# nRF5340.net
KiCad netlist of a schematic drawn in Altium Designer
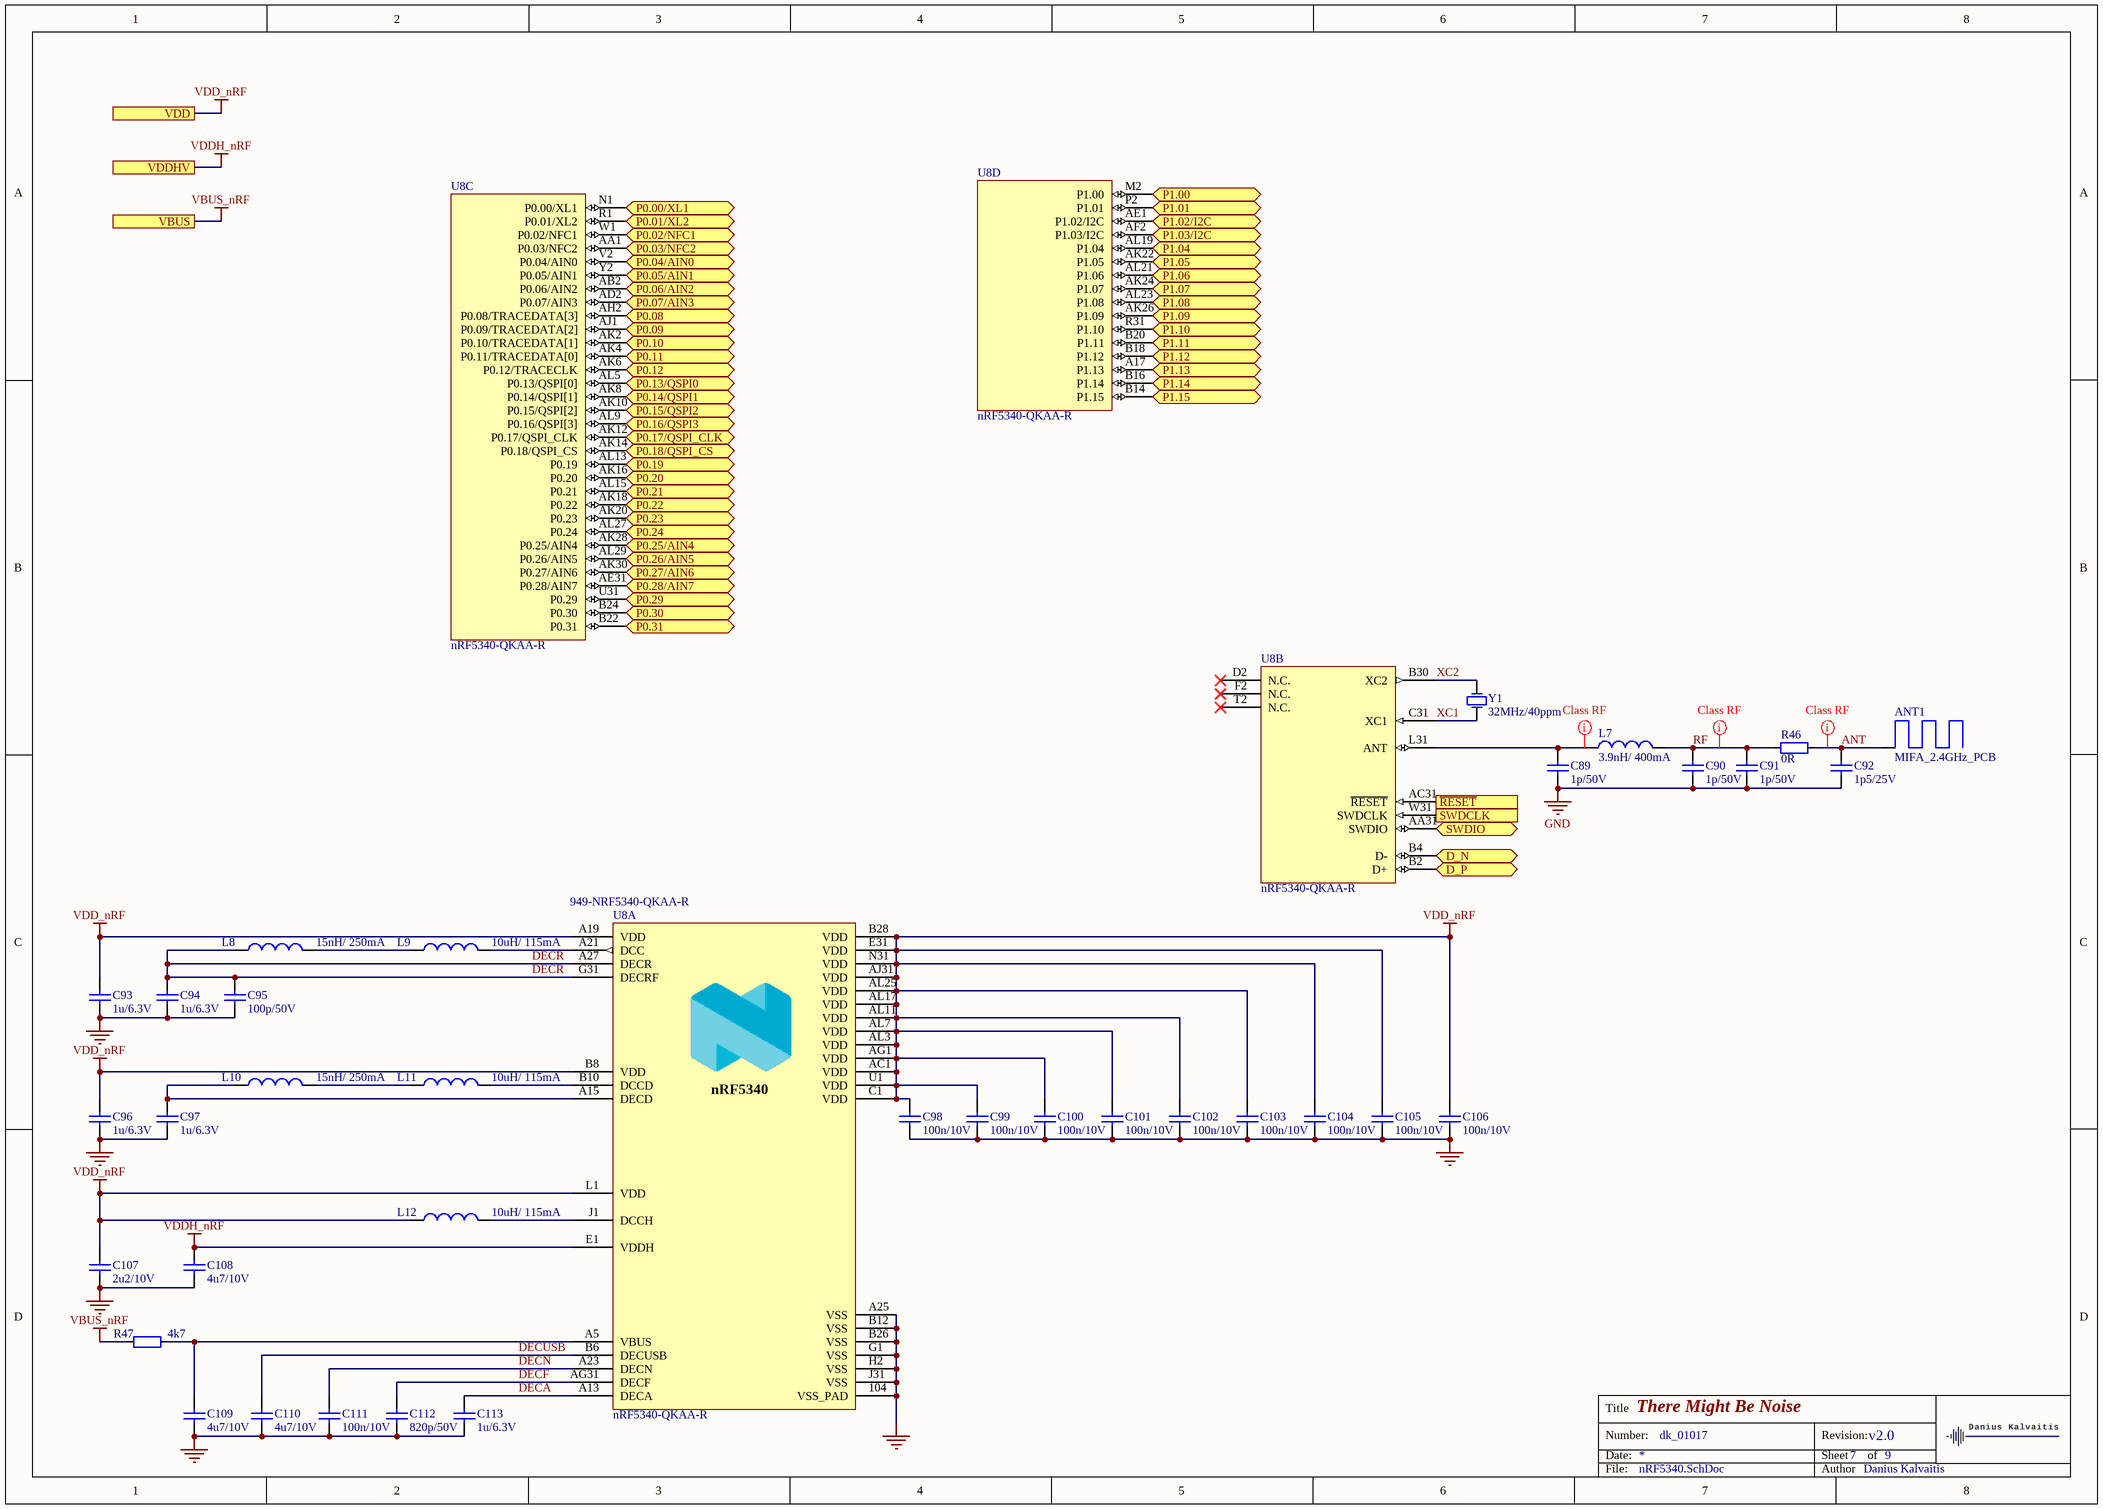
[diagram p0: nRF5340.SchDoc]

(export (version "E")
  (design (tool "Eeschema 10.0.6"))
  (components
    (comp (ref "ANT1")
      (value "MIFA_2.4GHz_PCB")
      (footprint "MIFA_2.4GHz_PCB2")
      (description "Meandered Inverted-F Antenna (MIFA)")
      (libsource (lib "altium-import") (part "root_0_MIFA_2.4GHz_PCB2_"))
    )
    (comp (ref "C89")
      (value "1p/50V")
      (footprint "C0201")
      (fields (field (name "VOLTAGE") "50V") (field (name "TOLERANCE") "10%"))
      (libsource (lib "dk_capacitors") (part "1p 50V C0G 0201"))
    )
    (comp (ref "C90")
      (value "1p/50V")
      (footprint "C0201")
      (fields (field (name "VOLTAGE") "50V") (field (name "TOLERANCE") "10%"))
      (libsource (lib "dk_capacitors") (part "1p 50V C0G 0201"))
    )
    (comp (ref "C91")
      (value "1p/50V")
      (footprint "C0201")
      (fields (field (name "VOLTAGE") "50V") (field (name "TOLERANCE") "10%"))
      (libsource (lib "dk_capacitors") (part "1p 50V C0G 0201"))
    )
    (comp (ref "C92")
      (value "1p5/25V")
      (footprint "C0201")
      (fields (field (name "VOLTAGE") "25V") (field (name "TOLERANCE") "7%"))
      (libsource (lib "dk_capacitors") (part "1p5 25V C0G 0201"))
    )
    (comp (ref "C93")
      (value "1u/6.3V")
      (footprint "C0402")
      (fields (field (name "VOLTAGE") "6.3V") (field (name "TOLERANCE") "10%"))
      (libsource (lib "dk_capacitors") (part "1u 6V3 X7R 0402"))
    )
    (comp (ref "C94")
      (value "1u/6.3V")
      (footprint "C0402")
      (fields (field (name "VOLTAGE") "6.3V") (field (name "TOLERANCE") "10%"))
      (libsource (lib "dk_capacitors") (part "1u 6V3 X7R 0402"))
    )
    (comp (ref "C95")
      (value "100p/50V")
      (footprint "C0201")
      (fields (field (name "VOLTAGE") "50V") (field (name "TOLERANCE") "10%"))
      (libsource (lib "dk_capacitors") (part "100p 50V X7R 0201"))
    )
    (comp (ref "C96")
      (value "1u/6.3V")
      (footprint "C0402")
      (fields (field (name "VOLTAGE") "6.3V") (field (name "TOLERANCE") "10%"))
      (libsource (lib "dk_capacitors") (part "1u 6V3 X7R 0402"))
    )
    (comp (ref "C97")
      (value "1u/6.3V")
      (footprint "C0402")
      (fields (field (name "VOLTAGE") "6.3V") (field (name "TOLERANCE") "10%"))
      (libsource (lib "dk_capacitors") (part "1u 6V3 X7R 0402"))
    )
    (comp (ref "C98")
      (value "100n/10V")
      (footprint "C0201")
      (fields (field (name "VOLTAGE") "10V") (field (name "TOLERANCE") "10%"))
      (libsource (lib "dk_capacitors") (part "100n 10V X5R 0201"))
    )
    (comp (ref "C99")
      (value "100n/10V")
      (footprint "C0201")
      (fields (field (name "VOLTAGE") "10V") (field (name "TOLERANCE") "10%"))
      (libsource (lib "dk_capacitors") (part "100n 10V X5R 0201"))
    )
    (comp (ref "C100")
      (value "100n/10V")
      (footprint "C0201")
      (fields (field (name "VOLTAGE") "10V") (field (name "TOLERANCE") "10%"))
      (libsource (lib "dk_capacitors") (part "100n 10V X5R 0201"))
    )
    (comp (ref "C101")
      (value "100n/10V")
      (footprint "C0201")
      (fields (field (name "VOLTAGE") "10V") (field (name "TOLERANCE") "10%"))
      (libsource (lib "dk_capacitors") (part "100n 10V X5R 0201"))
    )
    (comp (ref "C102")
      (value "100n/10V")
      (footprint "C0201")
      (fields (field (name "VOLTAGE") "10V") (field (name "TOLERANCE") "10%"))
      (libsource (lib "dk_capacitors") (part "100n 10V X5R 0201"))
    )
    (comp (ref "C103")
      (value "100n/10V")
      (footprint "C0201")
      (fields (field (name "VOLTAGE") "10V") (field (name "TOLERANCE") "10%"))
      (libsource (lib "dk_capacitors") (part "100n 10V X5R 0201"))
    )
    (comp (ref "C104")
      (value "100n/10V")
      (footprint "C0201")
      (fields (field (name "VOLTAGE") "10V") (field (name "TOLERANCE") "10%"))
      (libsource (lib "dk_capacitors") (part "100n 10V X5R 0201"))
    )
    (comp (ref "C105")
      (value "100n/10V")
      (footprint "C0201")
      (fields (field (name "VOLTAGE") "10V") (field (name "TOLERANCE") "10%"))
      (libsource (lib "dk_capacitors") (part "100n 10V X5R 0201"))
    )
    (comp (ref "C106")
      (value "100n/10V")
      (footprint "C0201")
      (fields (field (name "VOLTAGE") "10V") (field (name "TOLERANCE") "10%"))
      (libsource (lib "dk_capacitors") (part "100n 10V X5R 0201"))
    )
    (comp (ref "C107")
      (value "2u2/10V")
      (footprint "C0603")
      (fields (field (name "VOLTAGE") "10V") (field (name "TOLERANCE") "10%"))
      (libsource (lib "dk_capacitors") (part "2u2 10V X5R 0603"))
    )
    (comp (ref "C108")
      (value "4u7/10V")
      (footprint "C0603")
      (fields (field (name "VOLTAGE") "10V") (field (name "TOLERANCE") "10%"))
      (libsource (lib "dk_capacitors") (part "4u7 10V X5R 0603"))
    )
    (comp (ref "C109")
      (value "4u7/10V")
      (footprint "C0603")
      (fields (field (name "VOLTAGE") "10V") (field (name "TOLERANCE") "10%"))
      (libsource (lib "dk_capacitors") (part "4u7 10V X5R 0603"))
    )
    (comp (ref "C110")
      (value "4u7/10V")
      (footprint "C0603")
      (fields (field (name "VOLTAGE") "10V") (field (name "TOLERANCE") "10%"))
      (libsource (lib "dk_capacitors") (part "4u7 10V X5R 0603"))
    )
    (comp (ref "C111")
      (value "100n/10V")
      (footprint "C0201")
      (fields (field (name "VOLTAGE") "10V") (field (name "TOLERANCE") "10%"))
      (libsource (lib "dk_capacitors") (part "100n 10V X5R 0201"))
    )
    (comp (ref "C112")
      (value "820p/50V")
      (footprint "C0201")
      (fields (field (name "VOLTAGE") "50V") (field (name "TOLERANCE") "10%"))
      (libsource (lib "dk_capacitors") (part "820p 50V X7R 0201"))
    )
    (comp (ref "C113")
      (value "1u/6.3V")
      (footprint "C0402")
      (fields (field (name "VOLTAGE") "6.3V") (field (name "TOLERANCE") "10%"))
      (libsource (lib "dk_capacitors") (part "1u 6V3 X7R 0402"))
    )
    (comp (ref "L7")
      (value "3.9nH/ 400mA")
      (footprint "L0201")
      (description "Fixed Inductors IND 0201 3.9nH Hi-Q SMD RF IND")
      (fields (field (name "TOLERANCE") "10%"))
      (libsource (lib "dk_inductors") (part "MLG0603P3N9ST000"))
    )
    (comp (ref "L8")
      (value "15nH/ 250mA")
      (footprint "L0201")
      (description "Fixed Inductors IND 0201 15nH Hi-Q SMD RF IND")
      (fields (field (name "TOLERANCE") "3%"))
      (libsource (lib "dk_inductors") (part "MLG0603P15NHT000"))
    )
    (comp (ref "L9")
      (value "10uH/ 115mA")
      (footprint "L0603")
      (description "Fixed Inductors 10uH 10% Wound Chip")
      (fields (field (name "TOLERANCE") "10%"))
      (libsource (lib "altium-import") (part "root_0_L0603B100KDWFT_"))
    )
    (comp (ref "L10")
      (value "15nH/ 250mA")
      (footprint "L0201")
      (description "Fixed Inductors IND 0201 15nH Hi-Q SMD RF IND")
      (fields (field (name "TOLERANCE") "3%"))
      (libsource (lib "dk_inductors") (part "MLG0603P15NHT000"))
    )
    (comp (ref "L11")
      (value "10uH/ 115mA")
      (footprint "L0603")
      (description "Fixed Inductors 10uH 10% Wound Chip")
      (fields (field (name "TOLERANCE") "10%"))
      (libsource (lib "altium-import") (part "root_0_L0603B100KDWFT_"))
    )
    (comp (ref "L12")
      (value "10uH/ 115mA")
      (footprint "L0603")
      (description "Fixed Inductors 10uH 10% Wound Chip")
      (fields (field (name "TOLERANCE") "10%"))
      (libsource (lib "altium-import") (part "root_0_L0603B100KDWFT_"))
    )
    (comp (ref "R46")
      (value "0R")
      (footprint "R0201")
      (fields (field (name "TOLERANCE") "1%") (field (name "VOLTAGE") "25V"))
      (libsource (lib "dk_resistors") (part "0R 50mW 25V 0201"))
    )
    (comp (ref "R47")
      (value "4k7")
      (footprint "R0402")
      (fields (field (name "TOLERANCE") "1%") (field (name "VOLTAGE") "50V"))
      (libsource (lib "dk_resistors") (part "4k7 63mW 50V 0402"))
    )
    (comp (ref "U8")
      (value "nRF5340-QKAA-R")
      (footprint "AQFN-94")
      (description "Multi-protocol Bluetooth Low Energy, IEEE 802.15.4, ANT and 2.4GHz proprietary system-on-chip")
      (fields (field (name "SUPPLIER PART NUMBER 1") "949-NRF5340-QKAA-R"))
      (libsource (lib "dk_ic_microcontrollers") (part "nRF5340-QKAA-R"))
    )
    (comp (ref "Y1")
      (value "32MHz/40ppm")
      (footprint "XTAL_2X1_6")
      (description "Crystals 2x1.6mm 32MHz 40ppm Crystal Unit")
      (fields (field (name "TOLERANCE") "40ppm"))
      (libsource (lib "dk_timing") (part "XRCGB32M000FXH2CR0"))
    )
  )
  (nets
    (net (code "1") (name "/ANT") (class "Default")
      (node (ref "ANT1") (pin "1") (pinfunction "1_1") (pintype "passive"))
      (node (ref "C92") (pin "2") (pinfunction "2_2") (pintype "passive"))
      (node (ref "R46") (pin "2") (pinfunction "2_2") (pintype "passive"))
    )
    (net (code "2") (name "/DECA") (class "Default")
      (node (ref "C113") (pin "2") (pinfunction "2_2") (pintype "passive"))
      (node (ref "U8") (pin "A13") (pinfunction "DECA_A13") (pintype "power_in"))
    )
    (net (code "3") (name "/DECF") (class "Default")
      (node (ref "C112") (pin "2") (pinfunction "2_2") (pintype "passive"))
      (node (ref "U8") (pin "AG31") (pinfunction "DECF_AG31") (pintype "power_in"))
    )
    (net (code "4") (name "/DECN") (class "Default")
      (node (ref "C111") (pin "2") (pinfunction "2_2") (pintype "passive"))
      (node (ref "U8") (pin "A23") (pinfunction "DECN_A23") (pintype "power_in"))
    )
    (net (code "5") (name "/DECR") (class "Default")
      (node (ref "C94") (pin "2") (pinfunction "2_2") (pintype "passive"))
      (node (ref "C95") (pin "2") (pinfunction "2_2") (pintype "passive"))
      (node (ref "L8") (pin "1") (pinfunction "1_1") (pintype "passive"))
      (node (ref "U8") (pin "A27") (pinfunction "DECR_A27") (pintype "power_in"))
      (node (ref "U8") (pin "G31") (pinfunction "DECRF_G31") (pintype "power_in"))
    )
    (net (code "6") (name "/DECUSB") (class "Default")
      (node (ref "C110") (pin "2") (pinfunction "2_2") (pintype "passive"))
      (node (ref "U8") (pin "B6") (pinfunction "DECUSB_B6") (pintype "power_in"))
    )
    (net (code "7") (name "/D_N") (class "Default")
      (node (ref "U8") (pin "B4") (pinfunction "D-_B4") (pintype "bidirectional"))
    )
    (net (code "8") (name "/D_P") (class "Default")
      (node (ref "U8") (pin "B2") (pinfunction "D+_B2") (pintype "bidirectional"))
    )
    (net (code "9") (name "/P0.00{slash}XL1") (class "Default")
      (node (ref "U8") (pin "N1") (pinfunction "P0.00/XL1_N1") (pintype "bidirectional"))
    )
    (net (code "10") (name "/P0.01{slash}XL2") (class "Default")
      (node (ref "U8") (pin "R1") (pinfunction "P0.01/XL2_R1") (pintype "bidirectional"))
    )
    (net (code "11") (name "/P0.02{slash}NFC1") (class "Default")
      (node (ref "U8") (pin "W1") (pinfunction "P0.02/NFC1_W1") (pintype "bidirectional"))
    )
    (net (code "12") (name "/P0.03{slash}NFC2") (class "Default")
      (node (ref "U8") (pin "AA1") (pinfunction "P0.03/NFC2_AA1") (pintype "bidirectional"))
    )
    (net (code "13") (name "/P0.04{slash}AIN0") (class "Default")
      (node (ref "U8") (pin "V2") (pinfunction "P0.04/AIN0_V2") (pintype "bidirectional"))
    )
    (net (code "14") (name "/P0.05{slash}AIN1") (class "Default")
      (node (ref "U8") (pin "Y2") (pinfunction "P0.05/AIN1_Y2") (pintype "bidirectional"))
    )
    (net (code "15") (name "/P0.06{slash}AIN2") (class "Default")
      (node (ref "U8") (pin "AB2") (pinfunction "P0.06/AIN2_AB2") (pintype "bidirectional"))
    )
    (net (code "16") (name "/P0.07{slash}AIN3") (class "Default")
      (node (ref "U8") (pin "AD2") (pinfunction "P0.07/AIN3_AD2") (pintype "bidirectional"))
    )
    (net (code "17") (name "/P0.08") (class "Default")
      (node (ref "U8") (pin "AH2") (pinfunction "P0.08/TRACEDATA[3]_AH2") (pintype "bidirectional"))
    )
    (net (code "18") (name "/P0.09") (class "Default")
      (node (ref "U8") (pin "AJ1") (pinfunction "P0.09/TRACEDATA[2]_AJ1") (pintype "bidirectional"))
    )
    (net (code "19") (name "/P0.10") (class "Default")
      (node (ref "U8") (pin "AK2") (pinfunction "P0.10/TRACEDATA[1]_AK2") (pintype "bidirectional"))
    )
    (net (code "20") (name "/P0.11") (class "Default")
      (node (ref "U8") (pin "AK4") (pinfunction "P0.11/TRACEDATA[0]_AK4") (pintype "bidirectional"))
    )
    (net (code "21") (name "/P0.12") (class "Default")
      (node (ref "U8") (pin "AK6") (pinfunction "P0.12/TRACECLK_AK6") (pintype "bidirectional"))
    )
    (net (code "22") (name "/P0.13{slash}QSPI0") (class "Default")
      (node (ref "U8") (pin "AL5") (pinfunction "P0.13/QSPI[0]_AL5") (pintype "bidirectional"))
    )
    (net (code "23") (name "/P0.14{slash}QSPI1") (class "Default")
      (node (ref "U8") (pin "AK8") (pinfunction "P0.14/QSPI[1]_AK8") (pintype "bidirectional"))
    )
    (net (code "24") (name "/P0.15{slash}QSPI2") (class "Default")
      (node (ref "U8") (pin "AK10") (pinfunction "P0.15/QSPI[2]_AK10") (pintype "bidirectional"))
    )
    (net (code "25") (name "/P0.16{slash}QSPI3") (class "Default")
      (node (ref "U8") (pin "AL9") (pinfunction "P0.16/QSPI[3]_AL9") (pintype "bidirectional"))
    )
    (net (code "26") (name "/P0.17{slash}QSPI_CLK") (class "Default")
      (node (ref "U8") (pin "AK12") (pinfunction "P0.17/QSPI_CLK_AK12") (pintype "bidirectional"))
    )
    (net (code "27") (name "/P0.18{slash}QSPI_CS") (class "Default")
      (node (ref "U8") (pin "AK14") (pinfunction "P0.18/QSPI_CS_AK14") (pintype "bidirectional"))
    )
    (net (code "28") (name "/P0.19") (class "Default")
      (node (ref "U8") (pin "AL13") (pinfunction "P0.19_AL13") (pintype "bidirectional"))
    )
    (net (code "29") (name "/P0.20") (class "Default")
      (node (ref "U8") (pin "AK16") (pinfunction "P0.20_AK16") (pintype "bidirectional"))
    )
    (net (code "30") (name "/P0.21") (class "Default")
      (node (ref "U8") (pin "AL15") (pinfunction "P0.21_AL15") (pintype "bidirectional"))
    )
    (net (code "31") (name "/P0.22") (class "Default")
      (node (ref "U8") (pin "AK18") (pinfunction "P0.22_AK18") (pintype "bidirectional"))
    )
    (net (code "32") (name "/P0.23") (class "Default")
      (node (ref "U8") (pin "AK20") (pinfunction "P0.23_AK20") (pintype "bidirectional"))
    )
    (net (code "33") (name "/P0.24") (class "Default")
      (node (ref "U8") (pin "AL27") (pinfunction "P0.24_AL27") (pintype "bidirectional"))
    )
    (net (code "34") (name "/P0.25{slash}AIN4") (class "Default")
      (node (ref "U8") (pin "AK28") (pinfunction "P0.25/AIN4_AK28") (pintype "bidirectional"))
    )
    (net (code "35") (name "/P0.26{slash}AIN5") (class "Default")
      (node (ref "U8") (pin "AL29") (pinfunction "P0.26/AIN5_AL29") (pintype "bidirectional"))
    )
    (net (code "36") (name "/P0.27{slash}AIN6") (class "Default")
      (node (ref "U8") (pin "AK30") (pinfunction "P0.27/AIN6_AK30") (pintype "bidirectional"))
    )
    (net (code "37") (name "/P0.28{slash}AIN7") (class "Default")
      (node (ref "U8") (pin "AE31") (pinfunction "P0.28/AIN7_AE31") (pintype "bidirectional"))
    )
    (net (code "38") (name "/P0.29") (class "Default")
      (node (ref "U8") (pin "U31") (pinfunction "P0.29_U31") (pintype "bidirectional"))
    )
    (net (code "39") (name "/P0.30") (class "Default")
      (node (ref "U8") (pin "B24") (pinfunction "P0.30_B24") (pintype "bidirectional"))
    )
    (net (code "40") (name "/P0.31") (class "Default")
      (node (ref "U8") (pin "B22") (pinfunction "P0.31_B22") (pintype "bidirectional"))
    )
    (net (code "41") (name "/P1.00") (class "Default")
      (node (ref "U8") (pin "M2") (pinfunction "P1.00_M2") (pintype "bidirectional"))
    )
    (net (code "42") (name "/P1.01") (class "Default")
      (node (ref "U8") (pin "P2") (pinfunction "P1.01_P2") (pintype "bidirectional"))
    )
    (net (code "43") (name "/P1.02{slash}I2C") (class "Default")
      (node (ref "U8") (pin "AE1") (pinfunction "P1.02/I2C_AE1") (pintype "bidirectional"))
    )
    (net (code "44") (name "/P1.03{slash}I2C") (class "Default")
      (node (ref "U8") (pin "AF2") (pinfunction "P1.03/I2C_AF2") (pintype "bidirectional"))
    )
    (net (code "45") (name "/P1.04") (class "Default")
      (node (ref "U8") (pin "AL19") (pinfunction "P1.04_AL19") (pintype "bidirectional"))
    )
    (net (code "46") (name "/P1.05") (class "Default")
      (node (ref "U8") (pin "AK22") (pinfunction "P1.05_AK22") (pintype "bidirectional"))
    )
    (net (code "47") (name "/P1.06") (class "Default")
      (node (ref "U8") (pin "AL21") (pinfunction "P1.06_AL21") (pintype "bidirectional"))
    )
    (net (code "48") (name "/P1.07") (class "Default")
      (node (ref "U8") (pin "AK24") (pinfunction "P1.07_AK24") (pintype "bidirectional"))
    )
    (net (code "49") (name "/P1.08") (class "Default")
      (node (ref "U8") (pin "AL23") (pinfunction "P1.08_AL23") (pintype "bidirectional"))
    )
    (net (code "50") (name "/P1.09") (class "Default")
      (node (ref "U8") (pin "AK26") (pinfunction "P1.09_AK26") (pintype "bidirectional"))
    )
    (net (code "51") (name "/P1.10") (class "Default")
      (node (ref "U8") (pin "R31") (pinfunction "P1.10_R31") (pintype "bidirectional"))
    )
    (net (code "52") (name "/P1.11") (class "Default")
      (node (ref "U8") (pin "B20") (pinfunction "P1.11_B20") (pintype "bidirectional"))
    )
    (net (code "53") (name "/P1.12") (class "Default")
      (node (ref "U8") (pin "B18") (pinfunction "P1.12_B18") (pintype "bidirectional"))
    )
    (net (code "54") (name "/P1.13") (class "Default")
      (node (ref "U8") (pin "A17") (pinfunction "P1.13_A17") (pintype "bidirectional"))
    )
    (net (code "55") (name "/P1.14") (class "Default")
      (node (ref "U8") (pin "B16") (pinfunction "P1.14_B16") (pintype "bidirectional"))
    )
    (net (code "56") (name "/P1.15") (class "Default")
      (node (ref "U8") (pin "B14") (pinfunction "P1.15_B14") (pintype "bidirectional"))
    )
    (net (code "57") (name "/RF") (class "Default")
      (node (ref "C90") (pin "2") (pinfunction "2_2") (pintype "passive"))
      (node (ref "C91") (pin "2") (pinfunction "2_2") (pintype "passive"))
      (node (ref "L7") (pin "2") (pinfunction "2_2") (pintype "passive"))
      (node (ref "R46") (pin "1") (pinfunction "1_1") (pintype "passive"))
    )
    (net (code "58") (name "/SWDCLK") (class "Default")
      (node (ref "U8") (pin "W31") (pinfunction "SWDCLK_W31") (pintype "input"))
    )
    (net (code "59") (name "/SWDIO") (class "Default")
      (node (ref "U8") (pin "AA31") (pinfunction "SWDIO_AA31") (pintype "bidirectional"))
    )
    (net (code "60") (name "/XC1") (class "Default")
      (node (ref "U8") (pin "C31") (pinfunction "XC1_C31") (pintype "input"))
      (node (ref "Y1") (pin "1") (pintype "passive"))
    )
    (net (code "61") (name "/XC2") (class "Default")
      (node (ref "U8") (pin "B30") (pinfunction "XC2_B30") (pintype "output"))
      (node (ref "Y1") (pin "3") (pintype "passive"))
    )
    (net (code "62") (name "/~{RESET}") (class "Default")
      (node (ref "U8") (pin "AC31") (pinfunction "~{RESET}_AC31") (pintype "input"))
    )
    (net (code "63") (name "GND") (class "Default")
      (node (ref "C100") (pin "1") (pinfunction "1_1") (pintype "passive"))
      (node (ref "C101") (pin "1") (pinfunction "1_1") (pintype "passive"))
      (node (ref "C102") (pin "1") (pinfunction "1_1") (pintype "passive"))
      (node (ref "C103") (pin "1") (pinfunction "1_1") (pintype "passive"))
      (node (ref "C104") (pin "1") (pinfunction "1_1") (pintype "passive"))
      (node (ref "C105") (pin "1") (pinfunction "1_1") (pintype "passive"))
      (node (ref "C106") (pin "1") (pinfunction "1_1") (pintype "passive"))
      (node (ref "C107") (pin "1") (pinfunction "1_1") (pintype "passive"))
      (node (ref "C108") (pin "1") (pinfunction "1_1") (pintype "passive"))
      (node (ref "C109") (pin "1") (pinfunction "1_1") (pintype "passive"))
      (node (ref "C110") (pin "1") (pinfunction "1_1") (pintype "passive"))
      (node (ref "C111") (pin "1") (pinfunction "1_1") (pintype "passive"))
      (node (ref "C112") (pin "1") (pinfunction "1_1") (pintype "passive"))
      (node (ref "C113") (pin "1") (pinfunction "1_1") (pintype "passive"))
      (node (ref "C89") (pin "1") (pinfunction "1_1") (pintype "passive"))
      (node (ref "C90") (pin "1") (pinfunction "1_1") (pintype "passive"))
      (node (ref "C91") (pin "1") (pinfunction "1_1") (pintype "passive"))
      (node (ref "C92") (pin "1") (pinfunction "1_1") (pintype "passive"))
      (node (ref "C93") (pin "1") (pinfunction "1_1") (pintype "passive"))
      (node (ref "C94") (pin "1") (pinfunction "1_1") (pintype "passive"))
      (node (ref "C95") (pin "1") (pinfunction "1_1") (pintype "passive"))
      (node (ref "C96") (pin "1") (pinfunction "1_1") (pintype "passive"))
      (node (ref "C97") (pin "1") (pinfunction "1_1") (pintype "passive"))
      (node (ref "C98") (pin "1") (pinfunction "1_1") (pintype "passive"))
      (node (ref "C99") (pin "1") (pinfunction "1_1") (pintype "passive"))
      (node (ref "U8") (pin "104") (pinfunction "VSS_PAD_104") (pintype "power_in"))
      (node (ref "U8") (pin "A25") (pinfunction "VSS_A25") (pintype "power_in"))
      (node (ref "U8") (pin "B12") (pinfunction "VSS_B12") (pintype "power_in"))
      (node (ref "U8") (pin "B26") (pinfunction "VSS_B26") (pintype "power_in"))
      (node (ref "U8") (pin "G1") (pinfunction "VSS_G1") (pintype "power_in"))
      (node (ref "U8") (pin "H2") (pinfunction "VSS_H2") (pintype "power_in"))
      (node (ref "U8") (pin "J31") (pinfunction "VSS_J31") (pintype "power_in"))
    )
    (net (code "64") (name "Net-(L8-Pad2)") (class "Default")
      (node (ref "L8") (pin "2") (pinfunction "2_2") (pintype "passive"))
      (node (ref "L9") (pin "1") (pinfunction "1_1") (pintype "passive"))
    )
    (net (code "65") (name "Net-(L10-Pad2)") (class "Default")
      (node (ref "L10") (pin "2") (pinfunction "2_2") (pintype "passive"))
      (node (ref "L11") (pin "1") (pinfunction "1_1") (pintype "passive"))
    )
    (net (code "66") (name "Net-(U8A-DCC)") (class "Default")
      (node (ref "L9") (pin "2") (pinfunction "2_2") (pintype "passive"))
      (node (ref "U8") (pin "A21") (pinfunction "DCC_A21") (pintype "output"))
    )
    (net (code "67") (name "Net-(U8A-DCCD)") (class "Default")
      (node (ref "L11") (pin "2") (pinfunction "2_2") (pintype "passive"))
      (node (ref "U8") (pin "B10") (pinfunction "DCCD_B10") (pintype "power_in"))
    )
    (net (code "68") (name "Net-(U8A-DCCH)") (class "Default")
      (node (ref "L12") (pin "2") (pinfunction "2_2") (pintype "passive"))
      (node (ref "U8") (pin "J1") (pinfunction "DCCH_J1") (pintype "power_in"))
    )
    (net (code "69") (name "Net-(U8A-DECD)") (class "Default")
      (node (ref "C97") (pin "2") (pinfunction "2_2") (pintype "passive"))
      (node (ref "L10") (pin "1") (pinfunction "1_1") (pintype "passive"))
      (node (ref "U8") (pin "A15") (pinfunction "DECD_A15") (pintype "power_in"))
    )
    (net (code "70") (name "Net-(U8A-VBUS)") (class "Default")
      (node (ref "C109") (pin "2") (pinfunction "2_2") (pintype "passive"))
      (node (ref "R47") (pin "2") (pinfunction "2_2") (pintype "passive"))
      (node (ref "U8") (pin "A5") (pinfunction "VBUS_A5") (pintype "power_in"))
    )
    (net (code "71") (name "Net-(U8B-ANT)") (class "Default")
      (node (ref "C89") (pin "2") (pinfunction "2_2") (pintype "passive"))
      (node (ref "L7") (pin "1") (pinfunction "1_1") (pintype "passive"))
      (node (ref "U8") (pin "L31") (pinfunction "ANT_L31") (pintype "bidirectional"))
    )
    (net (code "72") (name "VBUS_nRF") (class "Default")
      (node (ref "R47") (pin "1") (pinfunction "1_1") (pintype "passive"))
    )
    (net (code "73") (name "VDDH_nRF") (class "Default")
      (node (ref "C108") (pin "2") (pinfunction "2_2") (pintype "passive"))
      (node (ref "U8") (pin "E1") (pinfunction "VDDH_E1") (pintype "power_in"))
    )
    (net (code "74") (name "VDD_nRF") (class "Default")
      (node (ref "C100") (pin "2") (pinfunction "2_2") (pintype "passive"))
      (node (ref "C101") (pin "2") (pinfunction "2_2") (pintype "passive"))
      (node (ref "C102") (pin "2") (pinfunction "2_2") (pintype "passive"))
      (node (ref "C103") (pin "2") (pinfunction "2_2") (pintype "passive"))
      (node (ref "C104") (pin "2") (pinfunction "2_2") (pintype "passive"))
      (node (ref "C105") (pin "2") (pinfunction "2_2") (pintype "passive"))
      (node (ref "C106") (pin "2") (pinfunction "2_2") (pintype "passive"))
      (node (ref "C107") (pin "2") (pinfunction "2_2") (pintype "passive"))
      (node (ref "C93") (pin "2") (pinfunction "2_2") (pintype "passive"))
      (node (ref "C96") (pin "2") (pinfunction "2_2") (pintype "passive"))
      (node (ref "C98") (pin "2") (pinfunction "2_2") (pintype "passive"))
      (node (ref "C99") (pin "2") (pinfunction "2_2") (pintype "passive"))
      (node (ref "L12") (pin "1") (pinfunction "1_1") (pintype "passive"))
      (node (ref "U8") (pin "A19") (pinfunction "VDD_A19") (pintype "power_in"))
      (node (ref "U8") (pin "AC1") (pinfunction "VDD_AC1") (pintype "power_in"))
      (node (ref "U8") (pin "AG1") (pinfunction "VDD_AG1") (pintype "power_in"))
      (node (ref "U8") (pin "AJ31") (pinfunction "VDD_AJ31") (pintype "power_in"))
      (node (ref "U8") (pin "AL11") (pinfunction "VDD_AL11") (pintype "power_in"))
      (node (ref "U8") (pin "AL17") (pinfunction "VDD_AL17") (pintype "power_in"))
      (node (ref "U8") (pin "AL25") (pinfunction "VDD_AL25") (pintype "power_in"))
      (node (ref "U8") (pin "AL3") (pinfunction "VDD_AL3") (pintype "power_in"))
      (node (ref "U8") (pin "AL7") (pinfunction "VDD_AL7") (pintype "power_in"))
      (node (ref "U8") (pin "B28") (pinfunction "VDD_B28") (pintype "power_in"))
      (node (ref "U8") (pin "B8") (pinfunction "VDD_B8") (pintype "power_in"))
      (node (ref "U8") (pin "C1") (pinfunction "VDD_C1") (pintype "power_in"))
      (node (ref "U8") (pin "E31") (pinfunction "VDD_E31") (pintype "power_in"))
      (node (ref "U8") (pin "L1") (pinfunction "VDD_L1") (pintype "power_in"))
      (node (ref "U8") (pin "N31") (pinfunction "VDD_N31") (pintype "power_in"))
      (node (ref "U8") (pin "U1") (pinfunction "VDD_U1") (pintype "power_in"))
    )
    (net (code "75") (name "unconnected-(U8B-N.C.-PadD2)") (class "Default")
      (node (ref "U8") (pin "D2") (pinfunction "N.C._D2") (pintype "passive+no_connect"))
    )
    (net (code "76") (name "unconnected-(U8B-N.C.-PadF2)") (class "Default")
      (node (ref "U8") (pin "F2") (pinfunction "N.C._F2") (pintype "passive+no_connect"))
    )
    (net (code "77") (name "unconnected-(U8B-N.C.-PadT2)") (class "Default")
      (node (ref "U8") (pin "T2") (pinfunction "N.C._T2") (pintype "passive+no_connect"))
    )
  )
)
